# 5V_PSU_Daniel_Eisen_rev0.net
KiCad netlist of a schematic drawn in Altium Designer
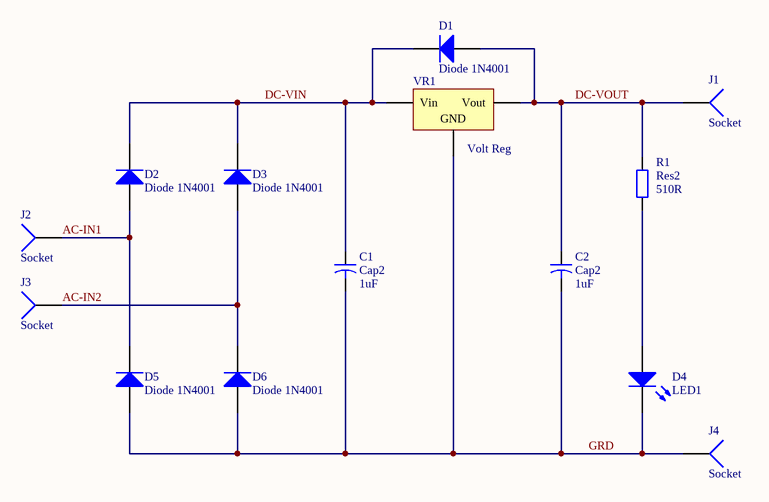
[diagram p0: 5V_PSU_Daniel_Eisen_rev0.SchDoc]

(export (version "E")
  (design (tool "Eeschema 10.0.6"))
  (components
    (comp (ref "C1")
      (value "Cap2")
      (footprint "CAPR5-4X5")
      (description "Capacitor")
      (fields (field (name "ALTIUM_VALUE") "1uF") (field (name "PUBLISHER") "Altium Limited"))
      (libsource (lib "Miscellaneous Devices") (part "Cap2"))
    )
    (comp (ref "C2")
      (value "Cap2")
      (footprint "CAPR5-4X5")
      (description "Capacitor")
      (fields (field (name "ALTIUM_VALUE") "1uF") (field (name "PUBLISHER") "Altium Limited"))
      (libsource (lib "Miscellaneous Devices") (part "Cap2"))
    )
    (comp (ref "D1")
      (value "Diode 1N4001")
      (footprint "DO-41")
      (description "1 Amp General Purpose Rectifier")
      (fields (field (name "PUBLISHER") "Altium Limited"))
      (libsource (lib "Miscellaneous Devices") (part "Diode 1N4001"))
    )
    (comp (ref "D2")
      (value "Diode 1N4001")
      (footprint "DO-41")
      (description "1 Amp General Purpose Rectifier")
      (fields (field (name "PUBLISHER") "Altium Limited"))
      (libsource (lib "Miscellaneous Devices") (part "Diode 1N4001"))
    )
    (comp (ref "D3")
      (value "Diode 1N4001")
      (footprint "DO-41")
      (description "1 Amp General Purpose Rectifier")
      (fields (field (name "PUBLISHER") "Altium Limited"))
      (libsource (lib "Miscellaneous Devices") (part "Diode 1N4001"))
    )
    (comp (ref "D4")
      (value "LED1")
      (footprint "LED-1")
      (description "Typical RED GaAs LED")
      (fields (field (name "PUBLISHER") "Altium Limited"))
      (libsource (lib "Miscellaneous Devices") (part "LED1"))
    )
    (comp (ref "D5")
      (value "Diode 1N4001")
      (footprint "DO-41")
      (description "1 Amp General Purpose Rectifier")
      (fields (field (name "PUBLISHER") "Altium Limited"))
      (libsource (lib "Miscellaneous Devices") (part "Diode 1N4001"))
    )
    (comp (ref "D6")
      (value "Diode 1N4001")
      (footprint "DO-41")
      (description "1 Amp General Purpose Rectifier")
      (fields (field (name "PUBLISHER") "Altium Limited"))
      (libsource (lib "Miscellaneous Devices") (part "Diode 1N4001"))
    )
    (comp (ref "J1")
      (value "Socket")
      (footprint "PIN1")
      (fields (field (name "PUBLISHER") "Altium Limited"))
      (libsource (lib "Miscellaneous Connectors") (part "Socket"))
    )
    (comp (ref "J2")
      (value "Socket")
      (footprint "PIN1")
      (fields (field (name "PUBLISHER") "Altium Limited"))
      (libsource (lib "Miscellaneous Connectors") (part "Socket"))
    )
    (comp (ref "J3")
      (value "Socket")
      (footprint "PIN1")
      (fields (field (name "PUBLISHER") "Altium Limited"))
      (libsource (lib "Miscellaneous Connectors") (part "Socket"))
    )
    (comp (ref "J4")
      (value "Socket")
      (footprint "PIN1")
      (fields (field (name "PUBLISHER") "Altium Limited"))
      (libsource (lib "Miscellaneous Connectors") (part "Socket"))
    )
    (comp (ref "R1")
      (value "Res2")
      (footprint "AXIAL-0.4")
      (description "Resistor")
      (fields (field (name "ALTIUM_VALUE") "510R") (field (name "PUBLISHER") "Altium Limited"))
      (libsource (lib "Miscellaneous Devices") (part "Res2"))
    )
    (comp (ref "VR1")
      (value "Volt Reg")
      (footprint "TO-220-AB")
      (description "Voltage Regulator")
      (fields (field (name "PUBLISHER") "Altium Limited"))
      (libsource (lib "Miscellaneous Devices") (part "Volt Reg"))
    )
  )
  (nets
    (net (code "1") (name "/AC-IN1") (class "Default")
      (node (ref "D2") (pin "1") (pinfunction "A_1") (pintype "passive"))
      (node (ref "D5") (pin "2") (pinfunction "K_2") (pintype "passive"))
      (node (ref "J2") (pin "1") (pinfunction "1_1") (pintype "passive"))
    )
    (net (code "2") (name "/AC-IN2") (class "Default")
      (node (ref "D3") (pin "1") (pinfunction "A_1") (pintype "passive"))
      (node (ref "D6") (pin "2") (pinfunction "K_2") (pintype "passive"))
      (node (ref "J3") (pin "1") (pinfunction "1_1") (pintype "passive"))
    )
    (net (code "3") (name "/DC-VIN") (class "Default")
      (node (ref "C1") (pin "1") (pinfunction "1_1") (pintype "passive"))
      (node (ref "D1") (pin "2") (pinfunction "K_2") (pintype "passive"))
      (node (ref "D2") (pin "2") (pinfunction "K_2") (pintype "passive"))
      (node (ref "D3") (pin "2") (pinfunction "K_2") (pintype "passive"))
      (node (ref "VR1") (pin "1") (pinfunction "Vin_1") (pintype "passive"))
    )
    (net (code "4") (name "/DC-VOUT") (class "Default")
      (node (ref "C2") (pin "1") (pinfunction "1_1") (pintype "passive"))
      (node (ref "D1") (pin "1") (pinfunction "A_1") (pintype "passive"))
      (node (ref "J1") (pin "1") (pinfunction "1_1") (pintype "passive"))
      (node (ref "R1") (pin "2") (pinfunction "2_2") (pintype "passive"))
      (node (ref "VR1") (pin "3") (pinfunction "Vout_3") (pintype "passive"))
    )
    (net (code "5") (name "/GRD") (class "Default")
      (node (ref "C1") (pin "2") (pinfunction "2_2") (pintype "passive"))
      (node (ref "C2") (pin "2") (pinfunction "2_2") (pintype "passive"))
      (node (ref "D4") (pin "2") (pinfunction "K_2") (pintype "passive"))
      (node (ref "D5") (pin "1") (pinfunction "A_1") (pintype "passive"))
      (node (ref "D6") (pin "1") (pinfunction "A_1") (pintype "passive"))
      (node (ref "J4") (pin "1") (pinfunction "1_1") (pintype "passive"))
      (node (ref "VR1") (pin "2") (pinfunction "GND_2") (pintype "passive"))
    )
    (net (code "6") (name "Net-(D4-A)") (class "Default")
      (node (ref "D4") (pin "1") (pinfunction "A_1") (pintype "passive"))
      (node (ref "R1") (pin "1") (pinfunction "1_1") (pintype "passive"))
    )
  )
)
